# Actuation.net
KiCad netlist of a schematic drawn in Altium Designer
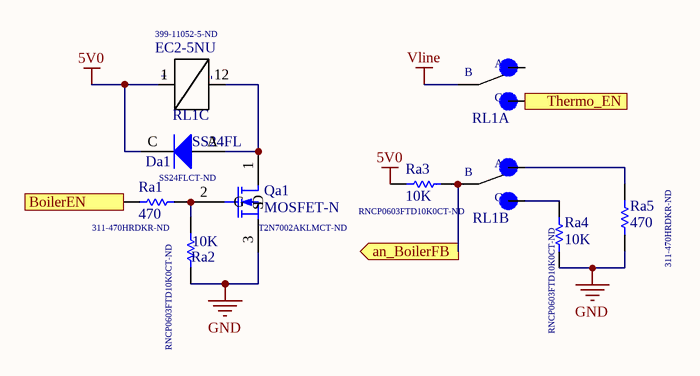
[diagram p0: Actuation.SchDoc]

(export (version "E")
  (design (tool "Eeschema 10.0.6"))
  (components
    (comp (ref "Da1")
      (value "SS24FL")
      (footprint "SOD123F")
      (description "Default Diode")
      (fields
        (field (name "SUPPLIER PART NUMBER 1") "SS24FLCT-ND")
        (field (name "PUBLISHER") "Altium Limited")
      )
      (libsource (lib "Miscellaneous Devices") (part "Diode"))
    )
    (comp (ref "Qa1")
      (value "MOSFET-N")
      (footprint "SOT23")
      (description "N-Channel MOSFET")
      (fields
        (field (name "SUPPLIER PART NUMBER 1") "T2N7002AKLMCT-ND")
        (field (name "PUBLISHER") "Altium Limited")
      )
      (libsource (lib "Miscellaneous Devices") (part "MOSFET-N"))
    )
    (comp (ref "Ra1")
      (value "470")
      (footprint "r0603")
      (description "Resistor")
      (fields
        (field (name "SUPPLIER PART NUMBER 1") "311-470HRDKR-ND")
        (field (name "Comment") "Res1")
        (field (name "PUBLISHER") "Altium Limited")
      )
      (libsource (lib "Miscellaneous Devices") (part "Res1"))
    )
    (comp (ref "Ra2")
      (value "10K")
      (footprint "r0603")
      (description "Resistor")
      (fields
        (field (name "SUPPLIER PART NUMBER 1") "RNCP0603FTD10K0CT-ND")
        (field (name "Comment") "Res1")
        (field (name "PUBLISHER") "Altium Limited")
      )
      (libsource (lib "Miscellaneous Devices") (part "Res1"))
    )
    (comp (ref "Ra3")
      (value "10K")
      (footprint "r0603")
      (description "Resistor")
      (fields
        (field (name "SUPPLIER PART NUMBER 1") "RNCP0603FTD10K0CT-ND")
        (field (name "Comment") "Res1")
        (field (name "PUBLISHER") "Altium Limited")
      )
      (libsource (lib "Miscellaneous Devices") (part "Res1"))
    )
    (comp (ref "Ra4")
      (value "10K")
      (footprint "r0603")
      (description "Resistor")
      (fields
        (field (name "SUPPLIER PART NUMBER 1") "RNCP0603FTD10K0CT-ND")
        (field (name "Comment") "Res1")
        (field (name "PUBLISHER") "Altium Limited")
      )
      (libsource (lib "Miscellaneous Devices") (part "Res1"))
    )
    (comp (ref "Ra5")
      (value "470")
      (footprint "r0603")
      (description "Resistor")
      (fields
        (field (name "SUPPLIER PART NUMBER 1") "311-470HRDKR-ND")
        (field (name "Comment") "Res1")
        (field (name "PUBLISHER") "Altium Limited")
      )
      (libsource (lib "Miscellaneous Devices") (part "Res1"))
    )
    (comp (ref "RL1")
      (value "EC2-5NU")
      (footprint "REL_EC2-5NU")
      (description "Electromechanical Relay DPDT 2A 5VDC 178Ohm Through Hole")
      (fields (field (name "MF") "KEMET") (field (name "SUPPLIER PART NUMBER 1") "399-11052-5-ND"))
      (libsource (lib "") (part "EC2-5NU_1"))
    )
  )
  (nets
    (net (code "1") (name "/BoilerEN") (class "Default")
      (node (ref "Ra1") (pin "2") (pinfunction "2_2") (pintype "passive"))
    )
    (net (code "2") (name "/Thermo_EN") (class "Default")
      (node (ref "RL1") (pin "5") (pinfunction "C1_5") (pintype "passive"))
    )
    (net (code "3") (name "/an_BoilerFB") (class "Default")
      (node (ref "RL1") (pin "9") (pinfunction "B_9") (pintype "passive"))
      (node (ref "Ra3") (pin "1") (pinfunction "1_1") (pintype "passive"))
    )
    (net (code "4") (name "5V0") (class "Default")
      (node (ref "Da1") (pin "C") (pinfunction "K_C") (pintype "passive"))
      (node (ref "RL1") (pin "1") (pinfunction "POS_1") (pintype "power_in"))
      (node (ref "Ra3") (pin "2") (pinfunction "2_2") (pintype "passive"))
    )
    (net (code "5") (name "GND") (class "Default")
      (node (ref "Qa1") (pin "3") (pinfunction "S_3") (pintype "passive"))
      (node (ref "Ra2") (pin "1") (pinfunction "1_1") (pintype "passive"))
      (node (ref "Ra4") (pin "2") (pinfunction "2_2") (pintype "passive"))
      (node (ref "Ra5") (pin "2") (pinfunction "2_2") (pintype "passive"))
    )
    (net (code "6") (name "Net-(Qa1-D)") (class "Default")
      (node (ref "Da1") (pin "A") (pinfunction "A_A") (pintype "passive"))
      (node (ref "Qa1") (pin "1") (pinfunction "D_1") (pintype "passive"))
      (node (ref "RL1") (pin "12") (pinfunction "NEG_12") (pintype "passive"))
    )
    (net (code "7") (name "Net-(Qa1-G)") (class "Default")
      (node (ref "Qa1") (pin "2") (pinfunction "G_2") (pintype "passive"))
      (node (ref "Ra1") (pin "1") (pinfunction "1_1") (pintype "passive"))
      (node (ref "Ra2") (pin "2") (pinfunction "2_2") (pintype "passive"))
    )
    (net (code "8") (name "Net-(RL1B-A)") (class "Default")
      (node (ref "RL1") (pin "10") (pinfunction "A_10") (pintype "passive"))
      (node (ref "Ra5") (pin "1") (pinfunction "1_1") (pintype "passive"))
    )
    (net (code "9") (name "Net-(RL1B-C)") (class "Default")
      (node (ref "RL1") (pin "8") (pinfunction "C_8") (pintype "passive"))
      (node (ref "Ra4") (pin "1") (pinfunction "1_1") (pintype "passive"))
    )
    (net (code "10") (name "Vline") (class "Default")
      (node (ref "RL1") (pin "4") (pinfunction "B1_4") (pintype "passive"))
    )
    (net (code "11") (name "unconnected-(RL1A-A1-Pad3)") (class "Default")
      (node (ref "RL1") (pin "3") (pinfunction "A1_3") (pintype "passive"))
    )
  )
)
